# keyboard_68.net
KiCad netlist of a schematic drawn in Altium Designer
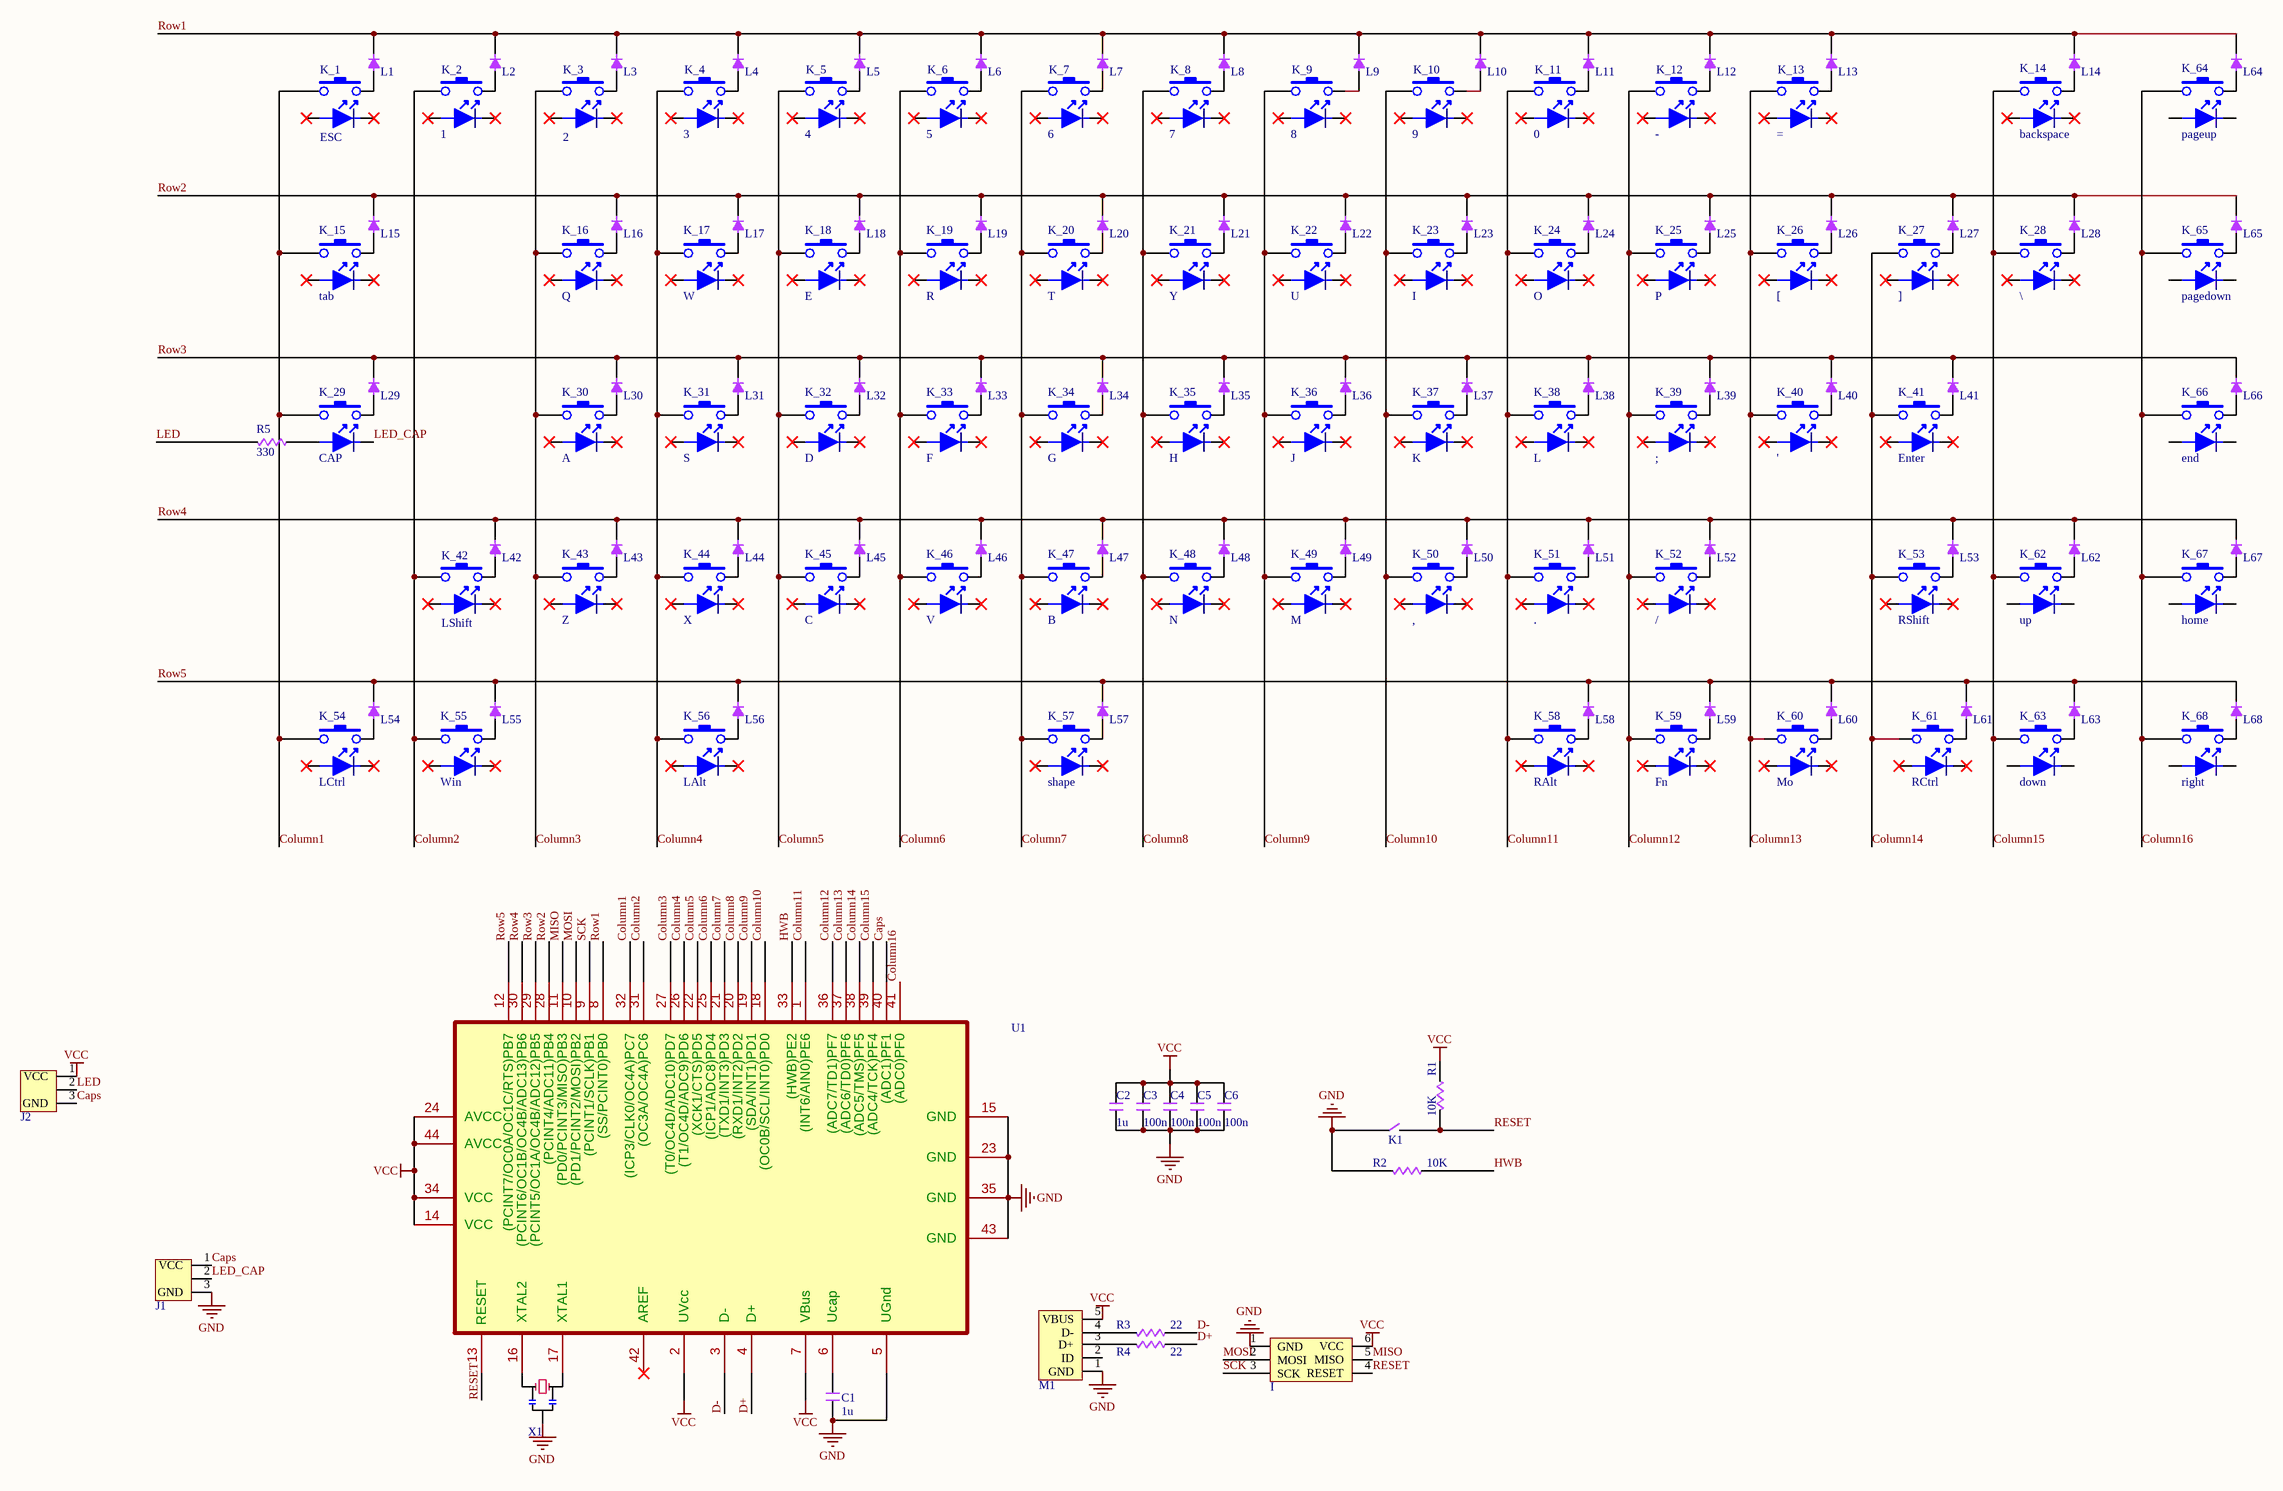
[diagram p0: keyboard_68.SchDoc]

(export (version "E")
  (design (tool "Eeschema 10.0.6"))
  (components
    (comp (ref "C1")
      (value "1u")
      (footprint "C_0603")
      (fields (field (name "Comment") "C"))
      (libsource (lib "Integrated_Library") (part "0603_C"))
    )
    (comp (ref "C2")
      (value "1u")
      (footprint "C_0603")
      (fields (field (name "Comment") "C"))
      (libsource (lib "Integrated_Library") (part "0603_C"))
    )
    (comp (ref "C3")
      (value "100n")
      (footprint "C_0603")
      (fields (field (name "Comment") "C"))
      (libsource (lib "Integrated_Library") (part "0603_C"))
    )
    (comp (ref "C4")
      (value "100n")
      (footprint "C_0603")
      (fields (field (name "Comment") "C"))
      (libsource (lib "Integrated_Library") (part "0603_C"))
    )
    (comp (ref "C5")
      (value "100n")
      (footprint "C_0603")
      (fields (field (name "Comment") "C"))
      (libsource (lib "Integrated_Library") (part "0603_C"))
    )
    (comp (ref "C6")
      (value "100n")
      (footprint "C_0603")
      (fields (field (name "Comment") "C"))
      (libsource (lib "Integrated_Library") (part "0603_C"))
    )
    (comp (ref "I") (value "ISP") (footprint "ISP") (libsource (lib "Integrated_Library") (part "ISP")))
    (comp (ref "J1") (value "Jump") (footprint "3PIN") (libsource (lib "Integrated_Library") (part "3PIN")))
    (comp (ref "J2") (value "Jump") (footprint "3PIN") (libsource (lib "Integrated_Library") (part "3PIN")))
    (comp (ref "K1") (value "SWITCH") (footprint "KEY") (libsource (lib "Integrated_Library") (part "KEY")))
    (comp (ref "K_1")
      (value "ESC")
      (footprint "CHERRY")
      (libsource (lib "Integrated_Library") (part "Cherry"))
    )
    (comp (ref "K_2") (value "1") (footprint "CHERRY") (libsource (lib "Integrated_Library") (part "Cherry")))
    (comp (ref "K_3") (value "2") (footprint "CHERRY") (libsource (lib "Integrated_Library") (part "Cherry")))
    (comp (ref "K_4") (value "3") (footprint "CHERRY") (libsource (lib "Integrated_Library") (part "Cherry")))
    (comp (ref "K_5") (value "4") (footprint "CHERRY") (libsource (lib "Integrated_Library") (part "Cherry")))
    (comp (ref "K_6") (value "5") (footprint "CHERRY") (libsource (lib "Integrated_Library") (part "Cherry")))
    (comp (ref "K_7") (value "6") (footprint "CHERRY") (libsource (lib "Integrated_Library") (part "Cherry")))
    (comp (ref "K_8") (value "7") (footprint "CHERRY") (libsource (lib "Integrated_Library") (part "Cherry")))
    (comp (ref "K_9") (value "8") (footprint "CHERRY") (libsource (lib "Integrated_Library") (part "Cherry")))
    (comp (ref "K_10")
      (value "9")
      (footprint "CHERRY")
      (libsource (lib "Integrated_Library") (part "Cherry"))
    )
    (comp (ref "K_11")
      (value "0")
      (footprint "CHERRY")
      (libsource (lib "Integrated_Library") (part "Cherry"))
    )
    (comp (ref "K_12")
      (value "-")
      (footprint "CHERRY")
      (libsource (lib "Integrated_Library") (part "Cherry"))
    )
    (comp (ref "K_13")
      (value "~")
      (footprint "CHERRY")
      (libsource (lib "Integrated_Library") (part "Cherry"))
    )
    (comp (ref "K_14")
      (value "backspace")
      (footprint "KEY_CAP")
      (libsource (lib "Integrated_Library") (part "SHIFT"))
    )
    (comp (ref "K_15")
      (value "tab")
      (footprint "CHERRY")
      (libsource (lib "Integrated_Library") (part "Cherry"))
    )
    (comp (ref "K_16")
      (value "Q")
      (footprint "CHERRY")
      (libsource (lib "Integrated_Library") (part "Cherry"))
    )
    (comp (ref "K_17")
      (value "W")
      (footprint "CHERRY")
      (libsource (lib "Integrated_Library") (part "Cherry"))
    )
    (comp (ref "K_18")
      (value "E")
      (footprint "CHERRY")
      (libsource (lib "Integrated_Library") (part "Cherry"))
    )
    (comp (ref "K_19")
      (value "R")
      (footprint "CHERRY")
      (libsource (lib "Integrated_Library") (part "Cherry"))
    )
    (comp (ref "K_20")
      (value "T")
      (footprint "CHERRY")
      (libsource (lib "Integrated_Library") (part "Cherry"))
    )
    (comp (ref "K_21")
      (value "Y")
      (footprint "CHERRY")
      (libsource (lib "Integrated_Library") (part "Cherry"))
    )
    (comp (ref "K_22")
      (value "U")
      (footprint "CHERRY")
      (libsource (lib "Integrated_Library") (part "Cherry"))
    )
    (comp (ref "K_23")
      (value "I")
      (footprint "CHERRY")
      (libsource (lib "Integrated_Library") (part "Cherry"))
    )
    (comp (ref "K_24")
      (value "O")
      (footprint "CHERRY")
      (libsource (lib "Integrated_Library") (part "Cherry"))
    )
    (comp (ref "K_25")
      (value "P")
      (footprint "CHERRY")
      (libsource (lib "Integrated_Library") (part "Cherry"))
    )
    (comp (ref "K_26")
      (value "[")
      (footprint "CHERRY")
      (libsource (lib "Integrated_Library") (part "Cherry"))
    )
    (comp (ref "K_27")
      (value "]")
      (footprint "CHERRY")
      (libsource (lib "Integrated_Library") (part "Cherry"))
    )
    (comp (ref "K_28")
      (value "\\")
      (footprint "CHERRY")
      (libsource (lib "Integrated_Library") (part "Cherry"))
    )
    (comp (ref "K_29")
      (value "CAP")
      (footprint "CHERRY")
      (libsource (lib "Integrated_Library") (part "Cherry"))
    )
    (comp (ref "K_30")
      (value "A")
      (footprint "CHERRY")
      (libsource (lib "Integrated_Library") (part "Cherry"))
    )
    (comp (ref "K_31")
      (value "S")
      (footprint "CHERRY")
      (libsource (lib "Integrated_Library") (part "Cherry"))
    )
    (comp (ref "K_32")
      (value "D")
      (footprint "CHERRY")
      (libsource (lib "Integrated_Library") (part "Cherry"))
    )
    (comp (ref "K_33")
      (value "F")
      (footprint "CHERRY")
      (libsource (lib "Integrated_Library") (part "Cherry"))
    )
    (comp (ref "K_34")
      (value "G")
      (footprint "CHERRY")
      (libsource (lib "Integrated_Library") (part "Cherry"))
    )
    (comp (ref "K_35")
      (value "H")
      (footprint "CHERRY")
      (libsource (lib "Integrated_Library") (part "Cherry"))
    )
    (comp (ref "K_36")
      (value "J")
      (footprint "CHERRY")
      (libsource (lib "Integrated_Library") (part "Cherry"))
    )
    (comp (ref "K_37")
      (value "K")
      (footprint "CHERRY")
      (libsource (lib "Integrated_Library") (part "Cherry"))
    )
    (comp (ref "K_38")
      (value "L")
      (footprint "CHERRY")
      (libsource (lib "Integrated_Library") (part "Cherry"))
    )
    (comp (ref "K_39")
      (value ";")
      (footprint "CHERRY")
      (libsource (lib "Integrated_Library") (part "Cherry"))
    )
    (comp (ref "K_40")
      (value "'")
      (footprint "CHERRY")
      (libsource (lib "Integrated_Library") (part "Cherry"))
    )
    (comp (ref "K_41")
      (value "Enter")
      (footprint "KEY_CAP")
      (libsource (lib "Integrated_Library") (part "SHIFT"))
    )
    (comp (ref "K_42")
      (value "LShift")
      (footprint "KEY_CAP")
      (libsource (lib "Integrated_Library") (part "SHIFT"))
    )
    (comp (ref "K_43")
      (value "Z")
      (footprint "CHERRY")
      (libsource (lib "Integrated_Library") (part "Cherry"))
    )
    (comp (ref "K_44")
      (value "X")
      (footprint "CHERRY")
      (libsource (lib "Integrated_Library") (part "Cherry"))
    )
    (comp (ref "K_45")
      (value "C")
      (footprint "CHERRY")
      (libsource (lib "Integrated_Library") (part "Cherry"))
    )
    (comp (ref "K_46")
      (value "V")
      (footprint "CHERRY")
      (libsource (lib "Integrated_Library") (part "Cherry"))
    )
    (comp (ref "K_47")
      (value "B")
      (footprint "CHERRY")
      (libsource (lib "Integrated_Library") (part "Cherry"))
    )
    (comp (ref "K_48")
      (value "N")
      (footprint "CHERRY")
      (libsource (lib "Integrated_Library") (part "Cherry"))
    )
    (comp (ref "K_49")
      (value "M")
      (footprint "CHERRY")
      (libsource (lib "Integrated_Library") (part "Cherry"))
    )
    (comp (ref "K_50")
      (value ",")
      (footprint "CHERRY")
      (libsource (lib "Integrated_Library") (part "Cherry"))
    )
    (comp (ref "K_51")
      (value ".")
      (footprint "CHERRY")
      (libsource (lib "Integrated_Library") (part "Cherry"))
    )
    (comp (ref "K_52")
      (value "/")
      (footprint "CHERRY")
      (libsource (lib "Integrated_Library") (part "Cherry"))
    )
    (comp (ref "K_53")
      (value "RShift")
      (footprint "KEY_CAP")
      (libsource (lib "Integrated_Library") (part "SHIFT"))
    )
    (comp (ref "K_54")
      (value "LCtrl")
      (footprint "CHERRY")
      (libsource (lib "Integrated_Library") (part "Cherry"))
    )
    (comp (ref "K_55")
      (value "Win")
      (footprint "CHERRY")
      (libsource (lib "Integrated_Library") (part "Cherry"))
    )
    (comp (ref "K_56")
      (value "LAlt")
      (footprint "CHERRY")
      (libsource (lib "Integrated_Library") (part "Cherry"))
    )
    (comp (ref "K_57")
      (value "shape")
      (footprint "SPACE_CAP")
      (libsource (lib "Integrated_Library") (part "shape"))
    )
    (comp (ref "K_58")
      (value "RAlt")
      (footprint "CHERRY")
      (libsource (lib "Integrated_Library") (part "Cherry"))
    )
    (comp (ref "K_59")
      (value "Fn")
      (footprint "CHERRY")
      (libsource (lib "Integrated_Library") (part "Cherry"))
    )
    (comp (ref "K_60")
      (value "Mo")
      (footprint "CHERRY")
      (libsource (lib "Integrated_Library") (part "Cherry"))
    )
    (comp (ref "K_61")
      (value "RCtrl")
      (footprint "CHERRY")
      (libsource (lib "Integrated_Library") (part "Cherry"))
    )
    (comp (ref "K_62")
      (value "up")
      (footprint "CHERRY")
      (libsource (lib "Integrated_Library") (part "Cherry"))
    )
    (comp (ref "K_63")
      (value "down")
      (footprint "CHERRY")
      (libsource (lib "Integrated_Library") (part "Cherry"))
    )
    (comp (ref "K_64")
      (value "pageup")
      (footprint "CHERRY")
      (libsource (lib "Integrated_Library") (part "Cherry"))
    )
    (comp (ref "K_65")
      (value "pagedown")
      (footprint "CHERRY")
      (libsource (lib "Integrated_Library") (part "Cherry"))
    )
    (comp (ref "K_66")
      (value "end")
      (footprint "CHERRY")
      (libsource (lib "Integrated_Library") (part "Cherry"))
    )
    (comp (ref "K_67")
      (value "home")
      (footprint "CHERRY")
      (libsource (lib "Integrated_Library") (part "Cherry"))
    )
    (comp (ref "K_68")
      (value "right")
      (footprint "CHERRY")
      (libsource (lib "Integrated_Library") (part "Cherry"))
    )
    (comp (ref "L1") (value "L") (footprint "L_0603") (libsource (lib "Integrated_Library") (part "0603_L")))
    (comp (ref "L2") (value "L") (footprint "L_0603") (libsource (lib "Integrated_Library") (part "0603_L")))
    (comp (ref "L3") (value "L") (footprint "L_0603") (libsource (lib "Integrated_Library") (part "0603_L")))
    (comp (ref "L4") (value "L") (footprint "L_0603") (libsource (lib "Integrated_Library") (part "0603_L")))
    (comp (ref "L5") (value "L") (footprint "L_0603") (libsource (lib "Integrated_Library") (part "0603_L")))
    (comp (ref "L6") (value "L") (footprint "L_0603") (libsource (lib "Integrated_Library") (part "0603_L")))
    (comp (ref "L7") (value "L") (footprint "L_0603") (libsource (lib "Integrated_Library") (part "0603_L")))
    (comp (ref "L8") (value "L") (footprint "L_0603") (libsource (lib "Integrated_Library") (part "0603_L")))
    (comp (ref "L9") (value "L") (footprint "L_0603") (libsource (lib "Integrated_Library") (part "0603_L")))
    (comp (ref "L10") (value "L") (footprint "L_0603") (libsource (lib "Integrated_Library") (part "0603_L")))
    (comp (ref "L11") (value "L") (footprint "L_0603") (libsource (lib "Integrated_Library") (part "0603_L")))
    (comp (ref "L12") (value "L") (footprint "L_0603") (libsource (lib "Integrated_Library") (part "0603_L")))
    (comp (ref "L13") (value "L") (footprint "L_0603") (libsource (lib "Integrated_Library") (part "0603_L")))
    (comp (ref "L14") (value "L") (footprint "L_0603") (libsource (lib "Integrated_Library") (part "0603_L")))
    (comp (ref "L15") (value "L") (footprint "L_0603") (libsource (lib "Integrated_Library") (part "0603_L")))
    (comp (ref "L16") (value "L") (footprint "L_0603") (libsource (lib "Integrated_Library") (part "0603_L")))
    (comp (ref "L17") (value "L") (footprint "L_0603") (libsource (lib "Integrated_Library") (part "0603_L")))
    (comp (ref "L18") (value "L") (footprint "L_0603") (libsource (lib "Integrated_Library") (part "0603_L")))
    (comp (ref "L19") (value "L") (footprint "L_0603") (libsource (lib "Integrated_Library") (part "0603_L")))
    (comp (ref "L20") (value "L") (footprint "L_0603") (libsource (lib "Integrated_Library") (part "0603_L")))
    (comp (ref "L21") (value "L") (footprint "L_0603") (libsource (lib "Integrated_Library") (part "0603_L")))
    (comp (ref "L22") (value "L") (footprint "L_0603") (libsource (lib "Integrated_Library") (part "0603_L")))
    (comp (ref "L23") (value "L") (footprint "L_0603") (libsource (lib "Integrated_Library") (part "0603_L")))
    (comp (ref "L24") (value "L") (footprint "L_0603") (libsource (lib "Integrated_Library") (part "0603_L")))
    (comp (ref "L25") (value "L") (footprint "L_0603") (libsource (lib "Integrated_Library") (part "0603_L")))
    (comp (ref "L26") (value "L") (footprint "L_0603") (libsource (lib "Integrated_Library") (part "0603_L")))
    (comp (ref "L27") (value "L") (footprint "L_0603") (libsource (lib "Integrated_Library") (part "0603_L")))
    (comp (ref "L28") (value "L") (footprint "L_0603") (libsource (lib "Integrated_Library") (part "0603_L")))
    (comp (ref "L29") (value "L") (footprint "L_0603") (libsource (lib "Integrated_Library") (part "0603_L")))
    (comp (ref "L30") (value "L") (footprint "L_0603") (libsource (lib "Integrated_Library") (part "0603_L")))
    (comp (ref "L31") (value "L") (footprint "L_0603") (libsource (lib "Integrated_Library") (part "0603_L")))
    (comp (ref "L32") (value "L") (footprint "L_0603") (libsource (lib "Integrated_Library") (part "0603_L")))
    (comp (ref "L33") (value "L") (footprint "L_0603") (libsource (lib "Integrated_Library") (part "0603_L")))
    (comp (ref "L34") (value "L") (footprint "L_0603") (libsource (lib "Integrated_Library") (part "0603_L")))
    (comp (ref "L35") (value "L") (footprint "L_0603") (libsource (lib "Integrated_Library") (part "0603_L")))
    (comp (ref "L36") (value "L") (footprint "L_0603") (libsource (lib "Integrated_Library") (part "0603_L")))
    (comp (ref "L37") (value "L") (footprint "L_0603") (libsource (lib "Integrated_Library") (part "0603_L")))
    (comp (ref "L38") (value "L") (footprint "L_0603") (libsource (lib "Integrated_Library") (part "0603_L")))
    (comp (ref "L39") (value "L") (footprint "L_0603") (libsource (lib "Integrated_Library") (part "0603_L")))
    (comp (ref "L40") (value "L") (footprint "L_0603") (libsource (lib "Integrated_Library") (part "0603_L")))
    (comp (ref "L41") (value "L") (footprint "L_0603") (libsource (lib "Integrated_Library") (part "0603_L")))
    (comp (ref "L42") (value "L") (footprint "L_0603") (libsource (lib "Integrated_Library") (part "0603_L")))
    (comp (ref "L43") (value "L") (footprint "L_0603") (libsource (lib "Integrated_Library") (part "0603_L")))
    (comp (ref "L44") (value "L") (footprint "L_0603") (libsource (lib "Integrated_Library") (part "0603_L")))
    (comp (ref "L45") (value "L") (footprint "L_0603") (libsource (lib "Integrated_Library") (part "0603_L")))
    (comp (ref "L46") (value "L") (footprint "L_0603") (libsource (lib "Integrated_Library") (part "0603_L")))
    (comp (ref "L47") (value "L") (footprint "L_0603") (libsource (lib "Integrated_Library") (part "0603_L")))
    (comp (ref "L48") (value "L") (footprint "L_0603") (libsource (lib "Integrated_Library") (part "0603_L")))
    (comp (ref "L49") (value "L") (footprint "L_0603") (libsource (lib "Integrated_Library") (part "0603_L")))
    (comp (ref "L50") (value "L") (footprint "L_0603") (libsource (lib "Integrated_Library") (part "0603_L")))
    (comp (ref "L51") (value "L") (footprint "L_0603") (libsource (lib "Integrated_Library") (part "0603_L")))
    (comp (ref "L52") (value "L") (footprint "L_0603") (libsource (lib "Integrated_Library") (part "0603_L")))
    (comp (ref "L53") (value "L") (footprint "L_0603") (libsource (lib "Integrated_Library") (part "0603_L")))
    (comp (ref "L54") (value "L") (footprint "L_0603") (libsource (lib "Integrated_Library") (part "0603_L")))
    (comp (ref "L55") (value "L") (footprint "L_0603") (libsource (lib "Integrated_Library") (part "0603_L")))
    (comp (ref "L56") (value "L") (footprint "L_0603") (libsource (lib "Integrated_Library") (part "0603_L")))
    (comp (ref "L57") (value "L") (footprint "L_0603") (libsource (lib "Integrated_Library") (part "0603_L")))
    (comp (ref "L58") (value "L") (footprint "L_0603") (libsource (lib "Integrated_Library") (part "0603_L")))
    (comp (ref "L59") (value "L") (footprint "L_0603") (libsource (lib "Integrated_Library") (part "0603_L")))
    (comp (ref "L60") (value "L") (footprint "L_0603") (libsource (lib "Integrated_Library") (part "0603_L")))
    (comp (ref "L61") (value "L") (footprint "L_0603") (libsource (lib "Integrated_Library") (part "0603_L")))
    (comp (ref "L62") (value "L") (footprint "L_0603") (libsource (lib "Integrated_Library") (part "0603_L")))
    (comp (ref "L63") (value "L") (footprint "L_0603") (libsource (lib "Integrated_Library") (part "0603_L")))
    (comp (ref "L64") (value "L") (footprint "L_0603") (libsource (lib "Integrated_Library") (part "0603_L")))
    (comp (ref "L65") (value "L") (footprint "L_0603") (libsource (lib "Integrated_Library") (part "0603_L")))
    (comp (ref "L66") (value "L") (footprint "L_0603") (libsource (lib "Integrated_Library") (part "0603_L")))
    (comp (ref "L67") (value "L") (footprint "L_0603") (libsource (lib "Integrated_Library") (part "0603_L")))
    (comp (ref "L68") (value "L") (footprint "L_0603") (libsource (lib "Integrated_Library") (part "0603_L")))
    (comp (ref "M1")
      (value "USB")
      (footprint "MICRO_USB")
      (libsource (lib "Integrated_Library") (part "MICRO_USB"))
    )
    (comp (ref "R1")
      (value "10K")
      (footprint "R_0603")
      (fields (field (name "Comment") "R"))
      (libsource (lib "Integrated_Library") (part "0603_R"))
    )
    (comp (ref "R2")
      (value "10K")
      (footprint "R_0603")
      (fields (field (name "Comment") "R"))
      (libsource (lib "Integrated_Library") (part "0603_R"))
    )
    (comp (ref "R3")
      (value "22")
      (footprint "R_0603")
      (fields (field (name "Comment") "R"))
      (libsource (lib "Integrated_Library") (part "0603_R"))
    )
    (comp (ref "R4")
      (value "22")
      (footprint "R_0603")
      (fields (field (name "Comment") "R"))
      (libsource (lib "Integrated_Library") (part "0603_R"))
    )
    (comp (ref "R5")
      (value "330")
      (footprint "R_0603")
      (fields (field (name "Comment") "R"))
      (libsource (lib "") (part "0603_R_1"))
    )
    (comp (ref "U1")
      (value "Atmega32U4")
      (footprint "TQFP80P1200X1200X120-44N")
      (libsource (lib "Integrated_Library") (part "LQFP44(ATMEGA32U4)"))
    )
    (comp (ref "X1")
      (value "CSTCE")
      (footprint "CSTCE")
      (libsource (lib "Integrated_Library") (part "CSTCE"))
    )
  )
  (nets
    (net (code "1") (name "/Caps") (class "Default")
      (node (ref "J1") (pin "1") (pinfunction "VCC_1") (pintype "passive"))
      (node (ref "J2") (pin "3") (pinfunction "GND_3") (pintype "passive"))
      (node (ref "U1") (pin "40") (pinfunction "(ADC1)PF1_40") (pintype "passive"))
    )
    (net (code "2") (name "/Column1") (class "Default")
      (node (ref "K_1") (pin "1") (pinfunction "1_1") (pintype "passive"))
      (node (ref "K_15") (pin "1") (pinfunction "1_1") (pintype "passive"))
      (node (ref "K_29") (pin "1") (pinfunction "1_1") (pintype "passive"))
      (node (ref "K_54") (pin "1") (pinfunction "1_1") (pintype "passive"))
      (node (ref "U1") (pin "32") (pinfunction "(ICP3/CLK0/OC4A)PC7_32") (pintype "passive"))
    )
    (net (code "3") (name "/Column2") (class "Default")
      (node (ref "K_2") (pin "1") (pinfunction "1_1") (pintype "passive"))
      (node (ref "K_42") (pin "1") (pinfunction "1_1") (pintype "passive"))
      (node (ref "K_55") (pin "1") (pinfunction "1_1") (pintype "passive"))
      (node (ref "U1") (pin "31") (pinfunction "(OC3A/OC4A)PC6_31") (pintype "passive"))
    )
    (net (code "4") (name "/Column3") (class "Default")
      (node (ref "K_16") (pin "1") (pinfunction "1_1") (pintype "passive"))
      (node (ref "K_3") (pin "1") (pinfunction "1_1") (pintype "passive"))
      (node (ref "K_30") (pin "1") (pinfunction "1_1") (pintype "passive"))
      (node (ref "K_43") (pin "1") (pinfunction "1_1") (pintype "passive"))
      (node (ref "U1") (pin "27") (pinfunction "(T0/OC4D/ADC10)PD7_27") (pintype "passive"))
    )
    (net (code "5") (name "/Column4") (class "Default")
      (node (ref "K_17") (pin "1") (pinfunction "1_1") (pintype "passive"))
      (node (ref "K_31") (pin "1") (pinfunction "1_1") (pintype "passive"))
      (node (ref "K_4") (pin "1") (pinfunction "1_1") (pintype "passive"))
      (node (ref "K_44") (pin "1") (pinfunction "1_1") (pintype "passive"))
      (node (ref "K_56") (pin "1") (pinfunction "1_1") (pintype "passive"))
      (node (ref "U1") (pin "26") (pinfunction "(T1/OC4D/ADC9)PD6_26") (pintype "passive"))
    )
    (net (code "6") (name "/Column5") (class "Default")
      (node (ref "K_18") (pin "1") (pinfunction "1_1") (pintype "passive"))
      (node (ref "K_32") (pin "1") (pinfunction "1_1") (pintype "passive"))
      (node (ref "K_45") (pin "1") (pinfunction "1_1") (pintype "passive"))
      (node (ref "K_5") (pin "1") (pinfunction "1_1") (pintype "passive"))
      (node (ref "U1") (pin "22") (pinfunction "(XCK1/CTS)PD5_22") (pintype "passive"))
    )
    (net (code "7") (name "/Column6") (class "Default")
      (node (ref "K_19") (pin "1") (pinfunction "1_1") (pintype "passive"))
      (node (ref "K_33") (pin "1") (pinfunction "1_1") (pintype "passive"))
      (node (ref "K_46") (pin "1") (pinfunction "1_1") (pintype "passive"))
      (node (ref "K_6") (pin "1") (pinfunction "1_1") (pintype "passive"))
      (node (ref "U1") (pin "25") (pinfunction "(ICP1/ADC8)PD4_25") (pintype "passive"))
    )
    (net (code "8") (name "/Column7") (class "Default")
      (node (ref "K_20") (pin "1") (pinfunction "1_1") (pintype "passive"))
      (node (ref "K_34") (pin "1") (pinfunction "1_1") (pintype "passive"))
      (node (ref "K_47") (pin "1") (pinfunction "1_1") (pintype "passive"))
      (node (ref "K_57") (pin "1") (pinfunction "1_1") (pintype "passive"))
      (node (ref "K_7") (pin "1") (pinfunction "1_1") (pintype "passive"))
      (node (ref "U1") (pin "21") (pinfunction "(TXD1/INT3)PD3_21") (pintype "passive"))
    )
    (net (code "9") (name "/Column8") (class "Default")
      (node (ref "K_21") (pin "1") (pinfunction "1_1") (pintype "passive"))
      (node (ref "K_35") (pin "1") (pinfunction "1_1") (pintype "passive"))
      (node (ref "K_48") (pin "1") (pinfunction "1_1") (pintype "passive"))
      (node (ref "K_8") (pin "1") (pinfunction "1_1") (pintype "passive"))
      (node (ref "U1") (pin "20") (pinfunction "(RXD1/INT2)PD2_20") (pintype "passive"))
    )
    (net (code "10") (name "/Column9") (class "Default")
      (node (ref "K_22") (pin "1") (pinfunction "1_1") (pintype "passive"))
      (node (ref "K_36") (pin "1") (pinfunction "1_1") (pintype "passive"))
      (node (ref "K_49") (pin "1") (pinfunction "1_1") (pintype "passive"))
      (node (ref "K_9") (pin "1") (pinfunction "1_1") (pintype "passive"))
      (node (ref "U1") (pin "19") (pinfunction "(SDA/INT1)PD1_19") (pintype "passive"))
    )
    (net (code "11") (name "/Column10") (class "Default")
      (node (ref "K_10") (pin "1") (pinfunction "1_1") (pintype "passive"))
      (node (ref "K_23") (pin "1") (pinfunction "1_1") (pintype "passive"))
      (node (ref "K_37") (pin "1") (pinfunction "1_1") (pintype "passive"))
      (node (ref "K_50") (pin "1") (pinfunction "1_1") (pintype "passive"))
      (node (ref "U1") (pin "18") (pinfunction "(OC0B/SCL/INT0)PD0_18") (pintype "passive"))
    )
    (net (code "12") (name "/Column11") (class "Default")
      (node (ref "K_11") (pin "1") (pinfunction "1_1") (pintype "passive"))
      (node (ref "K_24") (pin "1") (pinfunction "1_1") (pintype "passive"))
      (node (ref "K_38") (pin "1") (pinfunction "1_1") (pintype "passive"))
      (node (ref "K_51") (pin "1") (pinfunction "1_1") (pintype "passive"))
      (node (ref "K_58") (pin "1") (pinfunction "1_1") (pintype "passive"))
      (node (ref "U1") (pin "1") (pinfunction "(INT6/AIN0)PE6_1") (pintype "passive"))
    )
    (net (code "13") (name "/Column12") (class "Default")
      (node (ref "K_12") (pin "1") (pinfunction "1_1") (pintype "passive"))
      (node (ref "K_25") (pin "1") (pinfunction "1_1") (pintype "passive"))
      (node (ref "K_39") (pin "1") (pinfunction "1_1") (pintype "passive"))
      (node (ref "K_52") (pin "1") (pinfunction "1_1") (pintype "passive"))
      (node (ref "K_59") (pin "1") (pinfunction "1_1") (pintype "passive"))
      (node (ref "U1") (pin "36") (pinfunction "(ADC7/TD1)PF7_36") (pintype "passive"))
    )
    (net (code "14") (name "/Column13") (class "Default")
      (node (ref "K_13") (pin "1") (pinfunction "1_1") (pintype "passive"))
      (node (ref "K_26") (pin "1") (pinfunction "1_1") (pintype "passive"))
      (node (ref "K_40") (pin "1") (pinfunction "1_1") (pintype "passive"))
      (node (ref "K_60") (pin "1") (pinfunction "1_1") (pintype "passive"))
      (node (ref "U1") (pin "37") (pinfunction "(ADC6/TD0)PF6_37") (pintype "passive"))
    )
    (net (code "15") (name "/Column14") (class "Default")
      (node (ref "K_27") (pin "1") (pinfunction "1_1") (pintype "passive"))
      (node (ref "K_41") (pin "1") (pinfunction "1_1") (pintype "passive"))
      (node (ref "K_53") (pin "1") (pinfunction "1_1") (pintype "passive"))
      (node (ref "K_61") (pin "1") (pinfunction "1_1") (pintype "passive"))
      (node (ref "U1") (pin "38") (pinfunction "(ADC5/TMS)PF5_38") (pintype "passive"))
    )
    (net (code "16") (name "/Column15") (class "Default")
      (node (ref "K_14") (pin "1") (pinfunction "1_1") (pintype "passive"))
      (node (ref "K_28") (pin "1") (pinfunction "1_1") (pintype "passive"))
      (node (ref "K_62") (pin "1") (pinfunction "1_1") (pintype "passive"))
      (node (ref "K_63") (pin "1") (pinfunction "1_1") (pintype "passive"))
      (node (ref "U1") (pin "39") (pinfunction "(ADC4/TCK)PF4_39") (pintype "passive"))
    )
    (net (code "17") (name "/Column16") (class "Default")
      (node (ref "K_64") (pin "1") (pinfunction "1_1") (pintype "passive"))
      (node (ref "K_65") (pin "1") (pinfunction "1_1") (pintype "passive"))
      (node (ref "K_66") (pin "1") (pinfunction "1_1") (pintype "passive"))
      (node (ref "K_67") (pin "1") (pinfunction "1_1") (pintype "passive"))
      (node (ref "K_68") (pin "1") (pinfunction "1_1") (pintype "passive"))
      (node (ref "U1") (pin "41") (pinfunction "(ADC0)PF0_41") (pintype "passive"))
    )
    (net (code "18") (name "/D+") (class "Default")
      (node (ref "R4") (pin "2") (pintype "passive"))
      (node (ref "U1") (pin "4") (pinfunction "D+_4") (pintype "passive"))
    )
    (net (code "19") (name "/D-") (class "Default")
      (node (ref "R3") (pin "2") (pintype "passive"))
      (node (ref "U1") (pin "3") (pinfunction "D-_3") (pintype "passive"))
    )
    (net (code "20") (name "/HWB") (class "Default")
      (node (ref "R2") (pin "2") (pintype "passive"))
      (node (ref "U1") (pin "33") (pinfunction "(HWB)PE2_33") (pintype "passive"))
    )
    (net (code "21") (name "/LED") (class "Default")
      (node (ref "J2") (pin "2") (pinfunction "MISO_2") (pintype "passive"))
      (node (ref "R5") (pin "1") (pintype "passive"))
    )
    (net (code "22") (name "/LED_CAP") (class "Default")
      (node (ref "J1") (pin "2") (pinfunction "MISO_2") (pintype "passive"))
      (node (ref "K_29") (pin "4") (pinfunction "4_4") (pintype "passive"))
    )
    (net (code "23") (name "/MISO") (class "Default")
      (node (ref "I") (pin "5") (pinfunction "MISO_5") (pintype "passive"))
      (node (ref "U1") (pin "11") (pinfunction "(PD0/PCINT3/MISO)PB3_11") (pintype "passive"))
    )
    (net (code "24") (name "/MOSI") (class "Default")
      (node (ref "I") (pin "2") (pinfunction "MOSI_2") (pintype "passive"))
      (node (ref "U1") (pin "10") (pinfunction "(PD1/PCINT2/MOSI)PB2_10") (pintype "passive"))
    )
    (net (code "25") (name "/RESET") (class "Default")
      (node (ref "I") (pin "4") (pinfunction "RESET_4") (pintype "passive"))
      (node (ref "K1") (pin "2") (pinfunction "off_2") (pintype "passive"))
      (node (ref "R1") (pin "1") (pintype "passive"))
      (node (ref "U1") (pin "13") (pinfunction "RESET_13") (pintype "passive"))
    )
    (net (code "26") (name "/Row1") (class "Default")
      (node (ref "L1") (pin "2") (pintype "passive"))
      (node (ref "L10") (pin "2") (pintype "passive"))
      (node (ref "L11") (pin "2") (pintype "passive"))
      (node (ref "L12") (pin "2") (pintype "passive"))
      (node (ref "L13") (pin "2") (pintype "passive"))
      (node (ref "L14") (pin "2") (pintype "passive"))
      (node (ref "L2") (pin "2") (pintype "passive"))
      (node (ref "L3") (pin "2") (pintype "passive"))
      (node (ref "L4") (pin "2") (pintype "passive"))
      (node (ref "L5") (pin "2") (pintype "passive"))
      (node (ref "L6") (pin "2") (pintype "passive"))
      (node (ref "L64") (pin "2") (pintype "passive"))
      (node (ref "L7") (pin "2") (pintype "passive"))
      (node (ref "L8") (pin "2") (pintype "passive"))
      (node (ref "L9") (pin "2") (pintype "passive"))
      (node (ref "U1") (pin "8") (pinfunction "(SS/PCINT0)PB0_8") (pintype "passive"))
    )
    (net (code "27") (name "/Row2") (class "Default")
      (node (ref "L15") (pin "2") (pintype "passive"))
      (node (ref "L16") (pin "2") (pintype "passive"))
      (node (ref "L17") (pin "2") (pintype "passive"))
      (node (ref "L18") (pin "2") (pintype "passive"))
      (node (ref "L19") (pin "2") (pintype "passive"))
      (node (ref "L20") (pin "2") (pintype "passive"))
      (node (ref "L21") (pin "2") (pintype "passive"))
      (node (ref "L22") (pin "2") (pintype "passive"))
      (node (ref "L23") (pin "2") (pintype "passive"))
      (node (ref "L24") (pin "2") (pintype "passive"))
      (node (ref "L25") (pin "2") (pintype "passive"))
      (node (ref "L26") (pin "2") (pintype "passive"))
      (node (ref "L27") (pin "2") (pintype "passive"))
      (node (ref "L28") (pin "2") (pintype "passive"))
      (node (ref "L65") (pin "2") (pintype "passive"))
      (node (ref "U1") (pin "28") (pinfunction "(PCINT4/ADC11)PB4_28") (pintype "passive"))
    )
    (net (code "28") (name "/Row3") (class "Default")
      (node (ref "L29") (pin "2") (pintype "passive"))
      (node (ref "L30") (pin "2") (pintype "passive"))
      (node (ref "L31") (pin "2") (pintype "passive"))
      (node (ref "L32") (pin "2") (pintype "passive"))
      (node (ref "L33") (pin "2") (pintype "passive"))
      (node (ref "L34") (pin "2") (pintype "passive"))
      (node (ref "L35") (pin "2") (pintype "passive"))
      (node (ref "L36") (pin "2") (pintype "passive"))
      (node (ref "L37") (pin "2") (pintype "passive"))
      (node (ref "L38") (pin "2") (pintype "passive"))
      (node (ref "L39") (pin "2") (pintype "passive"))
      (node (ref "L40") (pin "2") (pintype "passive"))
      (node (ref "L41") (pin "2") (pintype "passive"))
      (node (ref "L66") (pin "2") (pintype "passive"))
      (node (ref "U1") (pin "29") (pinfunction "(PCINT5/OC1A/OC4B/ADC12)PB5_29") (pintype "passive"))
    )
    (net (code "29") (name "/Row4") (class "Default")
      (node (ref "L42") (pin "2") (pintype "passive"))
      (node (ref "L43") (pin "2") (pintype "passive"))
      (node (ref "L44") (pin "2") (pintype "passive"))
      (node (ref "L45") (pin "2") (pintype "passive"))
      (node (ref "L46") (pin "2") (pintype "passive"))
      (node (ref "L47") (pin "2") (pintype "passive"))
      (node (ref "L48") (pin "2") (pintype "passive"))
      (node (ref "L49") (pin "2") (pintype "passive"))
      (node (ref "L50") (pin "2") (pintype "passive"))
      (node (ref "L51") (pin "2") (pintype "passive"))
      (node (ref "L52") (pin "2") (pintype "passive"))
      (node (ref "L53") (pin "2") (pintype "passive"))
      (node (ref "L62") (pin "2") (pintype "passive"))
      (node (ref "L67") (pin "2") (pintype "passive"))
      (node (ref "U1") (pin "30") (pinfunction "(PCINT6/OC1B/OC4B/ADC13)PB6_30") (pintype "passive"))
    )
    (net (code "30") (name "/Row5") (class "Default")
      (node (ref "L54") (pin "2") (pintype "passive"))
      (node (ref "L55") (pin "2") (pintype "passive"))
      (node (ref "L56") (pin "2") (pintype "passive"))
      (node (ref "L57") (pin "2") (pintype "passive"))
      (node (ref "L58") (pin "2") (pintype "passive"))
      (node (ref "L59") (pin "2") (pintype "passive"))
      (node (ref "L60") (pin "2") (pintype "passive"))
      (node (ref "L61") (pin "2") (pintype "passive"))
      (node (ref "L63") (pin "2") (pintype "passive"))
      (node (ref "L68") (pin "2") (pintype "passive"))
      (node (ref "U1") (pin "12") (pinfunction "(PCINT7/OC0A/OC1C/RTS)PB7_12") (pintype "passive"))
    )
    (net (code "31") (name "/SCK") (class "Default")
      (node (ref "I") (pin "3") (pinfunction "SCK_3") (pintype "passive"))
      (node (ref "U1") (pin "9") (pinfunction "(PCINT1/SCLK)PB1_9") (pintype "passive"))
    )
    (net (code "32") (name "GND") (class "Default")
      (node (ref "C1") (pin "1") (pintype "passive"))
      (node (ref "C2") (pin "1") (pintype "passive"))
      (node (ref "C3") (pin "1") (pintype "passive"))
      (node (ref "C4") (pin "1") (pintype "passive"))
      (node (ref "C5") (pin "1") (pintype "passive"))
      (node (ref "C6") (pin "1") (pintype "passive"))
      (node (ref "I") (pin "1") (pinfunction "GND_1") (pintype "passive"))
      (node (ref "J1") (pin "3") (pinfunction "GND_3") (pintype "passive"))
      (node (ref "K1") (pin "1") (pinfunction "on_1") (pintype "passive"))
      (node (ref "M1") (pin "1") (pinfunction "GND_1") (pintype "passive"))
      (node (ref "R2") (pin "1") (pintype "passive"))
      (node (ref "U1") (pin "15") (pinfunction "GND_15") (pintype "passive"))
      (node (ref "U1") (pin "23") (pinfunction "GND_23") (pintype "passive"))
      (node (ref "U1") (pin "35") (pinfunction "GND_35") (pintype "passive"))
      (node (ref "U1") (pin "43") (pinfunction "GND_43") (pintype "passive"))
      (node (ref "U1") (pin "5") (pinfunction "UGnd_5") (pintype "passive"))
      (node (ref "X1") (pin "2") (pinfunction "GND_2") (pintype "passive"))
    )
    (net (code "33") (name "Net-(K_29-Pad3)") (class "Default")
      (node (ref "K_29") (pin "3") (pinfunction "3_3") (pintype "passive"))
      (node (ref "R5") (pin "2") (pintype "passive"))
    )
    (net (code "34") (name "Net-(L1-+)") (class "Default")
      (node (ref "K_1") (pin "2") (pinfunction "2_2") (pintype "passive"))
      (node (ref "L1") (pin "1") (pinfunction "+_1") (pintype "passive"))
    )
    (net (code "35") (name "Net-(L2-+)") (class "Default")
      (node (ref "K_2") (pin "2") (pinfunction "2_2") (pintype "passive"))
      (node (ref "L2") (pin "1") (pinfunction "+_1") (pintype "passive"))
    )
    (net (code "36") (name "Net-(L3-+)") (class "Default")
      (node (ref "K_3") (pin "2") (pinfunction "2_2") (pintype "passive"))
      (node (ref "L3") (pin "1") (pinfunction "+_1") (pintype "passive"))
    )
    (net (code "37") (name "Net-(L4-+)") (class "Default")
      (node (ref "K_4") (pin "2") (pinfunction "2_2") (pintype "passive"))
      (node (ref "L4") (pin "1") (pinfunction "+_1") (pintype "passive"))
    )
    (net (code "38") (name "Net-(L5-+)") (class "Default")
      (node (ref "K_5") (pin "2") (pinfunction "2_2") (pintype "passive"))
      (node (ref "L5") (pin "1") (pinfunction "+_1") (pintype "passive"))
    )
    (net (code "39") (name "Net-(L6-+)") (class "Default")
      (node (ref "K_6") (pin "2") (pinfunction "2_2") (pintype "passive"))
      (node (ref "L6") (pin "1") (pinfunction "+_1") (pintype "passive"))
    )
    (net (code "40") (name "Net-(L7-+)") (class "Default")
      (node (ref "K_7") (pin "2") (pinfunction "2_2") (pintype "passive"))
      (node (ref "L7") (pin "1") (pinfunction "+_1") (pintype "passive"))
    )
    (net (code "41") (name "Net-(L8-+)") (class "Default")
      (node (ref "K_8") (pin "2") (pinfunction "2_2") (pintype "passive"))
      (node (ref "L8") (pin "1") (pinfunction "+_1") (pintype "passive"))
    )
    (net (code "42") (name "Net-(L9-+)") (class "Default")
      (node (ref "K_9") (pin "2") (pinfunction "2_2") (pintype "passive"))
      (node (ref "L9") (pin "1") (pinfunction "+_1") (pintype "passive"))
    )
    (net (code "43") (name "Net-(L10-+)") (class "Default")
      (node (ref "K_10") (pin "2") (pinfunction "2_2") (pintype "passive"))
      (node (ref "L10") (pin "1") (pinfunction "+_1") (pintype "passive"))
    )
    (net (code "44") (name "Net-(L11-+)") (class "Default")
      (node (ref "K_11") (pin "2") (pinfunction "2_2") (pintype "passive"))
      (node (ref "L11") (pin "1") (pinfunction "+_1") (pintype "passive"))
    )
    (net (code "45") (name "Net-(L12-+)") (class "Default")
      (node (ref "K_12") (pin "2") (pinfunction "2_2") (pintype "passive"))
      (node (ref "L12") (pin "1") (pinfunction "+_1") (pintype "passive"))
    )
    (net (code "46") (name "Net-(L13-+)") (class "Default")
      (node (ref "K_13") (pin "2") (pinfunction "2_2") (pintype "passive"))
      (node (ref "L13") (pin "1") (pinfunction "+_1") (pintype "passive"))
    )
    (net (code "47") (name "Net-(L14-+)") (class "Default")
      (node (ref "K_14") (pin "2") (pinfunction "2_2") (pintype "passive"))
      (node (ref "L14") (pin "1") (pinfunction "+_1") (pintype "passive"))
    )
    (net (code "48") (name "Net-(L15-+)") (class "Default")
      (node (ref "K_15") (pin "2") (pinfunction "2_2") (pintype "passive"))
      (node (ref "L15") (pin "1") (pinfunction "+_1") (pintype "passive"))
    )
    (net (code "49") (name "Net-(L16-+)") (class "Default")
      (node (ref "K_16") (pin "2") (pinfunction "2_2") (pintype "passive"))
      (node (ref "L16") (pin "1") (pinfunction "+_1") (pintype "passive"))
    )
    (net (code "50") (name "Net-(L17-+)") (class "Default")
      (node (ref "K_17") (pin "2") (pinfunction "2_2") (pintype "passive"))
      (node (ref "L17") (pin "1") (pinfunction "+_1") (pintype "passive"))
    )
    (net (code "51") (name "Net-(L18-+)") (class "Default")
      (node (ref "K_18") (pin "2") (pinfunction "2_2") (pintype "passive"))
      (node (ref "L18") (pin "1") (pinfunction "+_1") (pintype "passive"))
    )
    (net (code "52") (name "Net-(L19-+)") (class "Default")
      (node (ref "K_19") (pin "2") (pinfunction "2_2") (pintype "passive"))
      (node (ref "L19") (pin "1") (pinfunction "+_1") (pintype "passive"))
    )
    (net (code "53") (name "Net-(L20-+)") (class "Default")
      (node (ref "K_20") (pin "2") (pinfunction "2_2") (pintype "passive"))
      (node (ref "L20") (pin "1") (pinfunction "+_1") (pintype "passive"))
    )
    (net (code "54") (name "Net-(L21-+)") (class "Default")
      (node (ref "K_21") (pin "2") (pinfunction "2_2") (pintype "passive"))
      (node (ref "L21") (pin "1") (pinfunction "+_1") (pintype "passive"))
    )
    (net (code "55") (name "Net-(L22-+)") (class "Default")
      (node (ref "K_22") (pin "2") (pinfunction "2_2") (pintype "passive"))
      (node (ref "L22") (pin "1") (pinfunction "+_1") (pintype "passive"))
    )
    (net (code "56") (name "Net-(L23-+)") (class "Default")
      (node (ref "K_23") (pin "2") (pinfunction "2_2") (pintype "passive"))
      (node (ref "L23") (pin "1") (pinfunction "+_1") (pintype "passive"))
    )
    (net (code "57") (name "Net-(L24-+)") (class "Default")
      (node (ref "K_24") (pin "2") (pinfunction "2_2") (pintype "passive"))
      (node (ref "L24") (pin "1") (pinfunction "+_1") (pintype "passive"))
    )
    (net (code "58") (name "Net-(L25-+)") (class "Default")
      (node (ref "K_25") (pin "2") (pinfunction "2_2") (pintype "passive"))
      (node (ref "L25") (pin "1") (pinfunction "+_1") (pintype "passive"))
    )
    (net (code "59") (name "Net-(L26-+)") (class "Default")
      (node (ref "K_26") (pin "2") (pinfunction "2_2") (pintype "passive"))
      (node (ref "L26") (pin "1") (pinfunction "+_1") (pintype "passive"))
    )
    (net (code "60") (name "Net-(L27-+)") (class "Default")
      (node (ref "K_27") (pin "2") (pinfunction "2_2") (pintype "passive"))
      (node (ref "L27") (pin "1") (pinfunction "+_1") (pintype "passive"))
    )
    (net (code "61") (name "Net-(L28-+)") (class "Default")
      (node (ref "K_28") (pin "2") (pinfunction "2_2") (pintype "passive"))
      (node (ref "L28") (pin "1") (pinfunction "+_1") (pintype "passive"))
    )
    (net (code "62") (name "Net-(L29-+)") (class "Default")
      (node (ref "K_29") (pin "2") (pinfunction "2_2") (pintype "passive"))
      (node (ref "L29") (pin "1") (pinfunction "+_1") (pintype "passive"))
    )
    (net (code "63") (name "Net-(L30-+)") (class "Default")
      (node (ref "K_30") (pin "2") (pinfunction "2_2") (pintype "passive"))
      (node (ref "L30") (pin "1") (pinfunction "+_1") (pintype "passive"))
    )
    (net (code "64") (name "Net-(L31-+)") (class "Default")
      (node (ref "K_31") (pin "2") (pinfunction "2_2") (pintype "passive"))
      (node (ref "L31") (pin "1") (pinfunction "+_1") (pintype "passive"))
    )
    (net (code "65") (name "Net-(L32-+)") (class "Default")
      (node (ref "K_32") (pin "2") (pinfunction "2_2") (pintype "passive"))
      (node (ref "L32") (pin "1") (pinfunction "+_1") (pintype "passive"))
    )
    (net (code "66") (name "Net-(L33-+)") (class "Default")
      (node (ref "K_33") (pin "2") (pinfunction "2_2") (pintype "passive"))
      (node (ref "L33") (pin "1") (pinfunction "+_1") (pintype "passive"))
    )
    (net (code "67") (name "Net-(L34-+)") (class "Default")
      (node (ref "K_34") (pin "2") (pinfunction "2_2") (pintype "passive"))
      (node (ref "L34") (pin "1") (pinfunction "+_1") (pintype "passive"))
    )
    (net (code "68") (name "Net-(L35-+)") (class "Default")
      (node (ref "K_35") (pin "2") (pinfunction "2_2") (pintype "passive"))
      (node (ref "L35") (pin "1") (pinfunction "+_1") (pintype "passive"))
    )
    (net (code "69") (name "Net-(L36-+)") (class "Default")
      (node (ref "K_36") (pin "2") (pinfunction "2_2") (pintype "passive"))
      (node (ref "L36") (pin "1") (pinfunction "+_1") (pintype "passive"))
    )
    (net (code "70") (name "Net-(L37-+)") (class "Default")
      (node (ref "K_37") (pin "2") (pinfunction "2_2") (pintype "passive"))
      (node (ref "L37") (pin "1") (pinfunction "+_1") (pintype "passive"))
    )
    (net (code "71") (name "Net-(L38-+)") (class "Default")
      (node (ref "K_38") (pin "2") (pinfunction "2_2") (pintype "passive"))
      (node (ref "L38") (pin "1") (pinfunction "+_1") (pintype "passive"))
    )
    (net (code "72") (name "Net-(L39-+)") (class "Default")
      (node (ref "K_39") (pin "2") (pinfunction "2_2") (pintype "passive"))
      (node (ref "L39") (pin "1") (pinfunction "+_1") (pintype "passive"))
    )
    (net (code "73") (name "Net-(L40-+)") (class "Default")
      (node (ref "K_40") (pin "2") (pinfunction "2_2") (pintype "passive"))
      (node (ref "L40") (pin "1") (pinfunction "+_1") (pintype "passive"))
    )
    (net (code "74") (name "Net-(L41-+)") (class "Default")
      (node (ref "K_41") (pin "2") (pinfunction "2_2") (pintype "passive"))
      (node (ref "L41") (pin "1") (pinfunction "+_1") (pintype "passive"))
    )
    (net (code "75") (name "Net-(L42-+)") (class "Default")
      (node (ref "K_42") (pin "2") (pinfunction "2_2") (pintype "passive"))
      (node (ref "L42") (pin "1") (pinfunction "+_1") (pintype "passive"))
    )
    (net (code "76") (name "Net-(L43-+)") (class "Default")
      (node (ref "K_43") (pin "2") (pinfunction "2_2") (pintype "passive"))
      (node (ref "L43") (pin "1") (pinfunction "+_1") (pintype "passive"))
    )
    (net (code "77") (name "Net-(L44-+)") (class "Default")
      (node (ref "K_44") (pin "2") (pinfunction "2_2") (pintype "passive"))
      (node (ref "L44") (pin "1") (pinfunction "+_1") (pintype "passive"))
    )
    (net (code "78") (name "Net-(L45-+)") (class "Default")
      (node (ref "K_45") (pin "2") (pinfunction "2_2") (pintype "passive"))
      (node (ref "L45") (pin "1") (pinfunction "+_1") (pintype "passive"))
    )
    (net (code "79") (name "Net-(L46-+)") (class "Default")
      (node (ref "K_46") (pin "2") (pinfunction "2_2") (pintype "passive"))
      (node (ref "L46") (pin "1") (pinfunction "+_1") (pintype "passive"))
    )
    (net (code "80") (name "Net-(L47-+)") (class "Default")
      (node (ref "K_47") (pin "2") (pinfunction "2_2") (pintype "passive"))
      (node (ref "L47") (pin "1") (pinfunction "+_1") (pintype "passive"))
    )
    (net (code "81") (name "Net-(L48-+)") (class "Default")
      (node (ref "K_48") (pin "2") (pinfunction "2_2") (pintype "passive"))
      (node (ref "L48") (pin "1") (pinfunction "+_1") (pintype "passive"))
    )
    (net (code "82") (name "Net-(L49-+)") (class "Default")
      (node (ref "K_49") (pin "2") (pinfunction "2_2") (pintype "passive"))
      (node (ref "L49") (pin "1") (pinfunction "+_1") (pintype "passive"))
    )
    (net (code "83") (name "Net-(L50-+)") (class "Default")
      (node (ref "K_50") (pin "2") (pinfunction "2_2") (pintype "passive"))
      (node (ref "L50") (pin "1") (pinfunction "+_1") (pintype "passive"))
    )
    (net (code "84") (name "Net-(L51-+)") (class "Default")
      (node (ref "K_51") (pin "2") (pinfunction "2_2") (pintype "passive"))
      (node (ref "L51") (pin "1") (pinfunction "+_1") (pintype "passive"))
    )
    (net (code "85") (name "Net-(L52-+)") (class "Default")
      (node (ref "K_52") (pin "2") (pinfunction "2_2") (pintype "passive"))
      (node (ref "L52") (pin "1") (pinfunction "+_1") (pintype "passive"))
    )
    (net (code "86") (name "Net-(L53-+)") (class "Default")
      (node (ref "K_53") (pin "2") (pinfunction "2_2") (pintype "passive"))
      (node (ref "L53") (pin "1") (pinfunction "+_1") (pintype "passive"))
    )
    (net (code "87") (name "Net-(L54-+)") (class "Default")
      (node (ref "K_54") (pin "2") (pinfunction "2_2") (pintype "passive"))
      (node (ref "L54") (pin "1") (pinfunction "+_1") (pintype "passive"))
    )
    (net (code "88") (name "Net-(L55-+)") (class "Default")
      (node (ref "K_55") (pin "2") (pinfunction "2_2") (pintype "passive"))
      (node (ref "L55") (pin "1") (pinfunction "+_1") (pintype "passive"))
    )
    (net (code "89") (name "Net-(L56-+)") (class "Default")
      (node (ref "K_56") (pin "2") (pinfunction "2_2") (pintype "passive"))
      (node (ref "L56") (pin "1") (pinfunction "+_1") (pintype "passive"))
    )
    (net (code "90") (name "Net-(L57-+)") (class "Default")
      (node (ref "K_57") (pin "2") (pinfunction "2_2") (pintype "passive"))
      (node (ref "L57") (pin "1") (pinfunction "+_1") (pintype "passive"))
    )
    (net (code "91") (name "Net-(L58-+)") (class "Default")
      (node (ref "K_58") (pin "2") (pinfunction "2_2") (pintype "passive"))
      (node (ref "L58") (pin "1") (pinfunction "+_1") (pintype "passive"))
    )
    (net (code "92") (name "Net-(L59-+)") (class "Default")
      (node (ref "K_59") (pin "2") (pinfunction "2_2") (pintype "passive"))
      (node (ref "L59") (pin "1") (pinfunction "+_1") (pintype "passive"))
    )
    (net (code "93") (name "Net-(L60-+)") (class "Default")
      (node (ref "K_60") (pin "2") (pinfunction "2_2") (pintype "passive"))
      (node (ref "L60") (pin "1") (pinfunction "+_1") (pintype "passive"))
    )
    (net (code "94") (name "Net-(L61-+)") (class "Default")
      (node (ref "K_61") (pin "2") (pinfunction "2_2") (pintype "passive"))
      (node (ref "L61") (pin "1") (pinfunction "+_1") (pintype "passive"))
    )
    (net (code "95") (name "Net-(L62-+)") (class "Default")
      (node (ref "K_62") (pin "2") (pinfunction "2_2") (pintype "passive"))
      (node (ref "L62") (pin "1") (pinfunction "+_1") (pintype "passive"))
    )
    (net (code "96") (name "Net-(L63-+)") (class "Default")
      (node (ref "K_63") (pin "2") (pinfunction "2_2") (pintype "passive"))
      (node (ref "L63") (pin "1") (pinfunction "+_1") (pintype "passive"))
    )
    (net (code "97") (name "Net-(L64-+)") (class "Default")
      (node (ref "K_64") (pin "2") (pinfunction "2_2") (pintype "passive"))
      (node (ref "L64") (pin "1") (pinfunction "+_1") (pintype "passive"))
    )
    (net (code "98") (name "Net-(L65-+)") (class "Default")
      (node (ref "K_65") (pin "2") (pinfunction "2_2") (pintype "passive"))
      (node (ref "L65") (pin "1") (pinfunction "+_1") (pintype "passive"))
    )
    (net (code "99") (name "Net-(L66-+)") (class "Default")
      (node (ref "K_66") (pin "2") (pinfunction "2_2") (pintype "passive"))
      (node (ref "L66") (pin "1") (pinfunction "+_1") (pintype "passive"))
    )
    (net (code "100") (name "Net-(L67-+)") (class "Default")
      (node (ref "K_67") (pin "2") (pinfunction "2_2") (pintype "passive"))
      (node (ref "L67") (pin "1") (pinfunction "+_1") (pintype "passive"))
    )
    (net (code "101") (name "Net-(L68-+)") (class "Default")
      (node (ref "K_68") (pin "2") (pinfunction "2_2") (pintype "passive"))
      (node (ref "L68") (pin "1") (pinfunction "+_1") (pintype "passive"))
    )
    (net (code "102") (name "Net-(M1-D+)") (class "Default")
      (node (ref "M1") (pin "3") (pinfunction "D+_3") (pintype "passive"))
      (node (ref "R4") (pin "1") (pintype "passive"))
    )
    (net (code "103") (name "Net-(M1-D-)") (class "Default")
      (node (ref "M1") (pin "4") (pinfunction "D-_4") (pintype "passive"))
      (node (ref "R3") (pin "1") (pintype "passive"))
    )
    (net (code "104") (name "Net-(U1-Ucap)") (class "Default")
      (node (ref "C1") (pin "2") (pintype "passive"))
      (node (ref "U1") (pin "6") (pinfunction "Ucap_6") (pintype "passive"))
    )
    (net (code "105") (name "Net-(U1-XTAL1)") (class "Default")
      (node (ref "U1") (pin "17") (pinfunction "XTAL1_17") (pintype "passive"))
      (node (ref "X1") (pin "3") (pinfunction "OUT_3") (pintype "passive"))
    )
    (net (code "106") (name "Net-(U1-XTAL2)") (class "Default")
      (node (ref "U1") (pin "16") (pinfunction "XTAL2_16") (pintype "passive"))
      (node (ref "X1") (pin "1") (pinfunction "IN_1") (pintype "passive"))
    )
    (net (code "107") (name "VCC") (class "Default")
      (node (ref "C2") (pin "2") (pintype "passive"))
      (node (ref "C3") (pin "2") (pintype "passive"))
      (node (ref "C4") (pin "2") (pintype "passive"))
      (node (ref "C5") (pin "2") (pintype "passive"))
      (node (ref "C6") (pin "2") (pintype "passive"))
      (node (ref "I") (pin "6") (pinfunction "VCC_6") (pintype "passive"))
      (node (ref "J2") (pin "1") (pinfunction "VCC_1") (pintype "passive"))
      (node (ref "M1") (pin "5") (pinfunction "VBUS_5") (pintype "passive"))
      (node (ref "R1") (pin "2") (pintype "passive"))
      (node (ref "U1") (pin "14") (pinfunction "VCC_14") (pintype "passive"))
      (node (ref "U1") (pin "2") (pinfunction "UVcc_2") (pintype "passive"))
      (node (ref "U1") (pin "24") (pinfunction "AVCC_24") (pintype "passive"))
      (node (ref "U1") (pin "34") (pinfunction "VCC_34") (pintype "passive"))
      (node (ref "U1") (pin "44") (pinfunction "AVCC_44") (pintype "passive"))
      (node (ref "U1") (pin "7") (pinfunction "VBus_7") (pintype "passive"))
    )
    (net (code "108") (name "unconnected-(K_1-Pad3)") (class "Default")
      (node (ref "K_1") (pin "3") (pinfunction "3_3") (pintype "passive+no_connect"))
    )
    (net (code "109") (name "unconnected-(K_1-Pad4)") (class "Default")
      (node (ref "K_1") (pin "4") (pinfunction "4_4") (pintype "passive+no_connect"))
    )
    (net (code "110") (name "unconnected-(K_2-Pad3)") (class "Default")
      (node (ref "K_2") (pin "3") (pinfunction "3_3") (pintype "passive+no_connect"))
    )
    (net (code "111") (name "unconnected-(K_2-Pad4)") (class "Default")
      (node (ref "K_2") (pin "4") (pinfunction "4_4") (pintype "passive+no_connect"))
    )
    (net (code "112") (name "unconnected-(K_3-Pad3)") (class "Default")
      (node (ref "K_3") (pin "3") (pinfunction "3_3") (pintype "passive+no_connect"))
    )
    (net (code "113") (name "unconnected-(K_3-Pad4)") (class "Default")
      (node (ref "K_3") (pin "4") (pinfunction "4_4") (pintype "passive+no_connect"))
    )
    (net (code "114") (name "unconnected-(K_4-Pad3)") (class "Default")
      (node (ref "K_4") (pin "3") (pinfunction "3_3") (pintype "passive+no_connect"))
    )
    (net (code "115") (name "unconnected-(K_4-Pad4)") (class "Default")
      (node (ref "K_4") (pin "4") (pinfunction "4_4") (pintype "passive+no_connect"))
    )
    (net (code "116") (name "unconnected-(K_5-Pad3)") (class "Default")
      (node (ref "K_5") (pin "3") (pinfunction "3_3") (pintype "passive+no_connect"))
    )
    (net (code "117") (name "unconnected-(K_5-Pad4)") (class "Default")
      (node (ref "K_5") (pin "4") (pinfunction "4_4") (pintype "passive+no_connect"))
    )
    (net (code "118") (name "unconnected-(K_6-Pad3)") (class "Default")
      (node (ref "K_6") (pin "3") (pinfunction "3_3") (pintype "passive+no_connect"))
    )
    (net (code "119") (name "unconnected-(K_6-Pad4)") (class "Default")
      (node (ref "K_6") (pin "4") (pinfunction "4_4") (pintype "passive+no_connect"))
    )
    (net (code "120") (name "unconnected-(K_7-Pad3)") (class "Default")
      (node (ref "K_7") (pin "3") (pinfunction "3_3") (pintype "passive+no_connect"))
    )
    (net (code "121") (name "unconnected-(K_7-Pad4)") (class "Default")
      (node (ref "K_7") (pin "4") (pinfunction "4_4") (pintype "passive+no_connect"))
    )
    (net (code "122") (name "unconnected-(K_8-Pad3)") (class "Default")
      (node (ref "K_8") (pin "3") (pinfunction "3_3") (pintype "passive+no_connect"))
    )
    (net (code "123") (name "unconnected-(K_8-Pad4)") (class "Default")
      (node (ref "K_8") (pin "4") (pinfunction "4_4") (pintype "passive+no_connect"))
    )
    (net (code "124") (name "unconnected-(K_9-Pad3)") (class "Default")
      (node (ref "K_9") (pin "3") (pinfunction "3_3") (pintype "passive+no_connect"))
    )
    (net (code "125") (name "unconnected-(K_9-Pad4)") (class "Default")
      (node (ref "K_9") (pin "4") (pinfunction "4_4") (pintype "passive+no_connect"))
    )
    (net (code "126") (name "unconnected-(K_10-Pad3)") (class "Default")
      (node (ref "K_10") (pin "3") (pinfunction "3_3") (pintype "passive+no_connect"))
    )
    (net (code "127") (name "unconnected-(K_10-Pad4)") (class "Default")
      (node (ref "K_10") (pin "4") (pinfunction "4_4") (pintype "passive+no_connect"))
    )
    (net (code "128") (name "unconnected-(K_11-Pad3)") (class "Default")
      (node (ref "K_11") (pin "3") (pinfunction "3_3") (pintype "passive+no_connect"))
    )
    (net (code "129") (name "unconnected-(K_11-Pad4)") (class "Default")
      (node (ref "K_11") (pin "4") (pinfunction "4_4") (pintype "passive+no_connect"))
    )
    (net (code "130") (name "unconnected-(K_12-Pad3)") (class "Default")
      (node (ref "K_12") (pin "3") (pinfunction "3_3") (pintype "passive+no_connect"))
    )
    (net (code "131") (name "unconnected-(K_12-Pad4)") (class "Default")
      (node (ref "K_12") (pin "4") (pinfunction "4_4") (pintype "passive+no_connect"))
    )
    (net (code "132") (name "unconnected-(K_13-Pad3)") (class "Default")
      (node (ref "K_13") (pin "3") (pinfunction "3_3") (pintype "passive+no_connect"))
    )
    (net (code "133") (name "unconnected-(K_13-Pad4)") (class "Default")
      (node (ref "K_13") (pin "4") (pinfunction "4_4") (pintype "passive+no_connect"))
    )
    (net (code "134") (name "unconnected-(K_14-Pad3)") (class "Default")
      (node (ref "K_14") (pin "3") (pinfunction "3_3") (pintype "passive+no_connect"))
    )
    (net (code "135") (name "unconnected-(K_14-Pad4)") (class "Default")
      (node (ref "K_14") (pin "4") (pinfunction "4_4") (pintype "passive+no_connect"))
    )
    (net (code "136") (name "unconnected-(K_15-Pad3)") (class "Default")
      (node (ref "K_15") (pin "3") (pinfunction "3_3") (pintype "passive+no_connect"))
    )
    (net (code "137") (name "unconnected-(K_15-Pad4)") (class "Default")
      (node (ref "K_15") (pin "4") (pinfunction "4_4") (pintype "passive+no_connect"))
    )
    (net (code "138") (name "unconnected-(K_16-Pad3)") (class "Default")
      (node (ref "K_16") (pin "3") (pinfunction "3_3") (pintype "passive+no_connect"))
    )
    (net (code "139") (name "unconnected-(K_16-Pad4)") (class "Default")
      (node (ref "K_16") (pin "4") (pinfunction "4_4") (pintype "passive+no_connect"))
    )
    (net (code "140") (name "unconnected-(K_17-Pad3)") (class "Default")
      (node (ref "K_17") (pin "3") (pinfunction "3_3") (pintype "passive+no_connect"))
    )
    (net (code "141") (name "unconnected-(K_17-Pad4)") (class "Default")
      (node (ref "K_17") (pin "4") (pinfunction "4_4") (pintype "passive+no_connect"))
    )
    (net (code "142") (name "unconnected-(K_18-Pad3)") (class "Default")
      (node (ref "K_18") (pin "3") (pinfunction "3_3") (pintype "passive+no_connect"))
    )
    (net (code "143") (name "unconnected-(K_18-Pad4)") (class "Default")
      (node (ref "K_18") (pin "4") (pinfunction "4_4") (pintype "passive+no_connect"))
    )
    (net (code "144") (name "unconnected-(K_19-Pad3)") (class "Default")
      (node (ref "K_19") (pin "3") (pinfunction "3_3") (pintype "passive+no_connect"))
    )
    (net (code "145") (name "unconnected-(K_19-Pad4)") (class "Default")
      (node (ref "K_19") (pin "4") (pinfunction "4_4") (pintype "passive+no_connect"))
    )
    (net (code "146") (name "unconnected-(K_20-Pad3)") (class "Default")
      (node (ref "K_20") (pin "3") (pinfunction "3_3") (pintype "passive+no_connect"))
    )
    (net (code "147") (name "unconnected-(K_20-Pad4)") (class "Default")
      (node (ref "K_20") (pin "4") (pinfunction "4_4") (pintype "passive+no_connect"))
    )
    (net (code "148") (name "unconnected-(K_21-Pad3)") (class "Default")
      (node (ref "K_21") (pin "3") (pinfunction "3_3") (pintype "passive+no_connect"))
    )
    (net (code "149") (name "unconnected-(K_21-Pad4)") (class "Default")
      (node (ref "K_21") (pin "4") (pinfunction "4_4") (pintype "passive+no_connect"))
    )
    (net (code "150") (name "unconnected-(K_22-Pad3)") (class "Default")
      (node (ref "K_22") (pin "3") (pinfunction "3_3") (pintype "passive+no_connect"))
    )
    (net (code "151") (name "unconnected-(K_22-Pad4)") (class "Default")
      (node (ref "K_22") (pin "4") (pinfunction "4_4") (pintype "passive+no_connect"))
    )
    (net (code "152") (name "unconnected-(K_23-Pad3)") (class "Default")
      (node (ref "K_23") (pin "3") (pinfunction "3_3") (pintype "passive+no_connect"))
    )
    (net (code "153") (name "unconnected-(K_23-Pad4)") (class "Default")
      (node (ref "K_23") (pin "4") (pinfunction "4_4") (pintype "passive+no_connect"))
    )
    (net (code "154") (name "unconnected-(K_24-Pad3)") (class "Default")
      (node (ref "K_24") (pin "3") (pinfunction "3_3") (pintype "passive+no_connect"))
    )
    (net (code "155") (name "unconnected-(K_24-Pad4)") (class "Default")
      (node (ref "K_24") (pin "4") (pinfunction "4_4") (pintype "passive+no_connect"))
    )
    (net (code "156") (name "unconnected-(K_25-Pad3)") (class "Default")
      (node (ref "K_25") (pin "3") (pinfunction "3_3") (pintype "passive+no_connect"))
    )
    (net (code "157") (name "unconnected-(K_25-Pad4)") (class "Default")
      (node (ref "K_25") (pin "4") (pinfunction "4_4") (pintype "passive+no_connect"))
    )
    (net (code "158") (name "unconnected-(K_26-Pad3)") (class "Default")
      (node (ref "K_26") (pin "3") (pinfunction "3_3") (pintype "passive+no_connect"))
    )
    (net (code "159") (name "unconnected-(K_26-Pad4)") (class "Default")
      (node (ref "K_26") (pin "4") (pinfunction "4_4") (pintype "passive+no_connect"))
    )
    (net (code "160") (name "unconnected-(K_27-Pad3)") (class "Default")
      (node (ref "K_27") (pin "3") (pinfunction "3_3") (pintype "passive+no_connect"))
    )
    (net (code "161") (name "unconnected-(K_27-Pad4)") (class "Default")
      (node (ref "K_27") (pin "4") (pinfunction "4_4") (pintype "passive+no_connect"))
    )
    (net (code "162") (name "unconnected-(K_28-Pad3)") (class "Default")
      (node (ref "K_28") (pin "3") (pinfunction "3_3") (pintype "passive+no_connect"))
    )
    (net (code "163") (name "unconnected-(K_28-Pad4)") (class "Default")
      (node (ref "K_28") (pin "4") (pinfunction "4_4") (pintype "passive+no_connect"))
    )
    (net (code "164") (name "unconnected-(K_30-Pad3)") (class "Default")
      (node (ref "K_30") (pin "3") (pinfunction "3_3") (pintype "passive+no_connect"))
    )
    (net (code "165") (name "unconnected-(K_30-Pad4)") (class "Default")
      (node (ref "K_30") (pin "4") (pinfunction "4_4") (pintype "passive+no_connect"))
    )
    (net (code "166") (name "unconnected-(K_31-Pad3)") (class "Default")
      (node (ref "K_31") (pin "3") (pinfunction "3_3") (pintype "passive+no_connect"))
    )
    (net (code "167") (name "unconnected-(K_31-Pad4)") (class "Default")
      (node (ref "K_31") (pin "4") (pinfunction "4_4") (pintype "passive+no_connect"))
    )
    (net (code "168") (name "unconnected-(K_32-Pad3)") (class "Default")
      (node (ref "K_32") (pin "3") (pinfunction "3_3") (pintype "passive+no_connect"))
    )
    (net (code "169") (name "unconnected-(K_32-Pad4)") (class "Default")
      (node (ref "K_32") (pin "4") (pinfunction "4_4") (pintype "passive+no_connect"))
    )
    (net (code "170") (name "unconnected-(K_33-Pad3)") (class "Default")
      (node (ref "K_33") (pin "3") (pinfunction "3_3") (pintype "passive+no_connect"))
    )
    (net (code "171") (name "unconnected-(K_33-Pad4)") (class "Default")
      (node (ref "K_33") (pin "4") (pinfunction "4_4") (pintype "passive+no_connect"))
    )
    (net (code "172") (name "unconnected-(K_34-Pad3)") (class "Default")
      (node (ref "K_34") (pin "3") (pinfunction "3_3") (pintype "passive+no_connect"))
    )
    (net (code "173") (name "unconnected-(K_34-Pad4)") (class "Default")
      (node (ref "K_34") (pin "4") (pinfunction "4_4") (pintype "passive+no_connect"))
    )
    (net (code "174") (name "unconnected-(K_35-Pad3)") (class "Default")
      (node (ref "K_35") (pin "3") (pinfunction "3_3") (pintype "passive+no_connect"))
    )
    (net (code "175") (name "unconnected-(K_35-Pad4)") (class "Default")
      (node (ref "K_35") (pin "4") (pinfunction "4_4") (pintype "passive+no_connect"))
    )
    (net (code "176") (name "unconnected-(K_36-Pad3)") (class "Default")
      (node (ref "K_36") (pin "3") (pinfunction "3_3") (pintype "passive+no_connect"))
    )
    (net (code "177") (name "unconnected-(K_36-Pad4)") (class "Default")
      (node (ref "K_36") (pin "4") (pinfunction "4_4") (pintype "passive+no_connect"))
    )
    (net (code "178") (name "unconnected-(K_37-Pad3)") (class "Default")
      (node (ref "K_37") (pin "3") (pinfunction "3_3") (pintype "passive+no_connect"))
    )
    (net (code "179") (name "unconnected-(K_37-Pad4)") (class "Default")
      (node (ref "K_37") (pin "4") (pinfunction "4_4") (pintype "passive+no_connect"))
    )
    (net (code "180") (name "unconnected-(K_38-Pad3)") (class "Default")
      (node (ref "K_38") (pin "3") (pinfunction "3_3") (pintype "passive+no_connect"))
    )
    (net (code "181") (name "unconnected-(K_38-Pad4)") (class "Default")
      (node (ref "K_38") (pin "4") (pinfunction "4_4") (pintype "passive+no_connect"))
    )
    (net (code "182") (name "unconnected-(K_39-Pad3)") (class "Default")
      (node (ref "K_39") (pin "3") (pinfunction "3_3") (pintype "passive+no_connect"))
    )
    (net (code "183") (name "unconnected-(K_39-Pad4)") (class "Default")
      (node (ref "K_39") (pin "4") (pinfunction "4_4") (pintype "passive+no_connect"))
    )
    (net (code "184") (name "unconnected-(K_40-Pad3)") (class "Default")
      (node (ref "K_40") (pin "3") (pinfunction "3_3") (pintype "passive+no_connect"))
    )
    (net (code "185") (name "unconnected-(K_40-Pad4)") (class "Default")
      (node (ref "K_40") (pin "4") (pinfunction "4_4") (pintype "passive+no_connect"))
    )
    (net (code "186") (name "unconnected-(K_41-Pad3)") (class "Default")
      (node (ref "K_41") (pin "3") (pinfunction "3_3") (pintype "passive+no_connect"))
    )
    (net (code "187") (name "unconnected-(K_41-Pad4)") (class "Default")
      (node (ref "K_41") (pin "4") (pinfunction "4_4") (pintype "passive+no_connect"))
    )
    (net (code "188") (name "unconnected-(K_42-Pad3)") (class "Default")
      (node (ref "K_42") (pin "3") (pinfunction "3_3") (pintype "passive+no_connect"))
    )
    (net (code "189") (name "unconnected-(K_42-Pad4)") (class "Default")
      (node (ref "K_42") (pin "4") (pinfunction "4_4") (pintype "passive+no_connect"))
    )
    (net (code "190") (name "unconnected-(K_43-Pad3)") (class "Default")
      (node (ref "K_43") (pin "3") (pinfunction "3_3") (pintype "passive+no_connect"))
    )
    (net (code "191") (name "unconnected-(K_43-Pad4)") (class "Default")
      (node (ref "K_43") (pin "4") (pinfunction "4_4") (pintype "passive+no_connect"))
    )
    (net (code "192") (name "unconnected-(K_44-Pad3)") (class "Default")
      (node (ref "K_44") (pin "3") (pinfunction "3_3") (pintype "passive+no_connect"))
    )
    (net (code "193") (name "unconnected-(K_44-Pad4)") (class "Default")
      (node (ref "K_44") (pin "4") (pinfunction "4_4") (pintype "passive+no_connect"))
    )
    (net (code "194") (name "unconnected-(K_45-Pad3)") (class "Default")
      (node (ref "K_45") (pin "3") (pinfunction "3_3") (pintype "passive+no_connect"))
    )
    (net (code "195") (name "unconnected-(K_45-Pad4)") (class "Default")
      (node (ref "K_45") (pin "4") (pinfunction "4_4") (pintype "passive+no_connect"))
    )
    (net (code "196") (name "unconnected-(K_46-Pad3)") (class "Default")
      (node (ref "K_46") (pin "3") (pinfunction "3_3") (pintype "passive+no_connect"))
    )
    (net (code "197") (name "unconnected-(K_46-Pad4)") (class "Default")
      (node (ref "K_46") (pin "4") (pinfunction "4_4") (pintype "passive+no_connect"))
    )
    (net (code "198") (name "unconnected-(K_47-Pad3)") (class "Default")
      (node (ref "K_47") (pin "3") (pinfunction "3_3") (pintype "passive+no_connect"))
    )
    (net (code "199") (name "unconnected-(K_47-Pad4)") (class "Default")
      (node (ref "K_47") (pin "4") (pinfunction "4_4") (pintype "passive+no_connect"))
    )
    (net (code "200") (name "unconnected-(K_48-Pad3)") (class "Default")
      (node (ref "K_48") (pin "3") (pinfunction "3_3") (pintype "passive+no_connect"))
    )
    (net (code "201") (name "unconnected-(K_48-Pad4)") (class "Default")
      (node (ref "K_48") (pin "4") (pinfunction "4_4") (pintype "passive+no_connect"))
    )
    (net (code "202") (name "unconnected-(K_49-Pad3)") (class "Default")
      (node (ref "K_49") (pin "3") (pinfunction "3_3") (pintype "passive+no_connect"))
    )
    (net (code "203") (name "unconnected-(K_49-Pad4)") (class "Default")
      (node (ref "K_49") (pin "4") (pinfunction "4_4") (pintype "passive+no_connect"))
    )
    (net (code "204") (name "unconnected-(K_50-Pad3)") (class "Default")
      (node (ref "K_50") (pin "3") (pinfunction "3_3") (pintype "passive+no_connect"))
    )
    (net (code "205") (name "unconnected-(K_50-Pad4)") (class "Default")
      (node (ref "K_50") (pin "4") (pinfunction "4_4") (pintype "passive+no_connect"))
    )
    (net (code "206") (name "unconnected-(K_51-Pad3)") (class "Default")
      (node (ref "K_51") (pin "3") (pinfunction "3_3") (pintype "passive+no_connect"))
    )
    (net (code "207") (name "unconnected-(K_51-Pad4)") (class "Default")
      (node (ref "K_51") (pin "4") (pinfunction "4_4") (pintype "passive+no_connect"))
    )
    (net (code "208") (name "unconnected-(K_52-Pad3)") (class "Default")
      (node (ref "K_52") (pin "3") (pinfunction "3_3") (pintype "passive+no_connect"))
    )
    (net (code "209") (name "unconnected-(K_52-Pad4)") (class "Default")
      (node (ref "K_52") (pin "4") (pinfunction "4_4") (pintype "passive+no_connect"))
    )
    (net (code "210") (name "unconnected-(K_53-Pad3)") (class "Default")
      (node (ref "K_53") (pin "3") (pinfunction "3_3") (pintype "passive+no_connect"))
    )
    (net (code "211") (name "unconnected-(K_53-Pad4)") (class "Default")
      (node (ref "K_53") (pin "4") (pinfunction "4_4") (pintype "passive+no_connect"))
    )
    (net (code "212") (name "unconnected-(K_54-Pad3)") (class "Default")
      (node (ref "K_54") (pin "3") (pinfunction "3_3") (pintype "passive+no_connect"))
    )
    (net (code "213") (name "unconnected-(K_54-Pad4)") (class "Default")
      (node (ref "K_54") (pin "4") (pinfunction "4_4") (pintype "passive+no_connect"))
    )
    (net (code "214") (name "unconnected-(K_55-Pad3)") (class "Default")
      (node (ref "K_55") (pin "3") (pinfunction "3_3") (pintype "passive+no_connect"))
    )
    (net (code "215") (name "unconnected-(K_55-Pad4)") (class "Default")
      (node (ref "K_55") (pin "4") (pinfunction "4_4") (pintype "passive+no_connect"))
    )
    (net (code "216") (name "unconnected-(K_56-Pad3)") (class "Default")
      (node (ref "K_56") (pin "3") (pinfunction "3_3") (pintype "passive+no_connect"))
    )
    (net (code "217") (name "unconnected-(K_56-Pad4)") (class "Default")
      (node (ref "K_56") (pin "4") (pinfunction "4_4") (pintype "passive+no_connect"))
    )
    (net (code "218") (name "unconnected-(K_57-Pad3)") (class "Default")
      (node (ref "K_57") (pin "3") (pinfunction "3_3") (pintype "passive+no_connect"))
    )
    (net (code "219") (name "unconnected-(K_57-Pad4)") (class "Default")
      (node (ref "K_57") (pin "4") (pinfunction "4_4") (pintype "passive+no_connect"))
    )
    (net (code "220") (name "unconnected-(K_58-Pad3)") (class "Default")
      (node (ref "K_58") (pin "3") (pinfunction "3_3") (pintype "passive+no_connect"))
    )
    (net (code "221") (name "unconnected-(K_58-Pad4)") (class "Default")
      (node (ref "K_58") (pin "4") (pinfunction "4_4") (pintype "passive+no_connect"))
    )
    (net (code "222") (name "unconnected-(K_59-Pad3)") (class "Default")
      (node (ref "K_59") (pin "3") (pinfunction "3_3") (pintype "passive+no_connect"))
    )
    (net (code "223") (name "unconnected-(K_59-Pad4)") (class "Default")
      (node (ref "K_59") (pin "4") (pinfunction "4_4") (pintype "passive+no_connect"))
    )
    (net (code "224") (name "unconnected-(K_60-Pad3)") (class "Default")
      (node (ref "K_60") (pin "3") (pinfunction "3_3") (pintype "passive+no_connect"))
    )
    (net (code "225") (name "unconnected-(K_60-Pad4)") (class "Default")
      (node (ref "K_60") (pin "4") (pinfunction "4_4") (pintype "passive+no_connect"))
    )
    (net (code "226") (name "unconnected-(K_61-Pad3)") (class "Default")
      (node (ref "K_61") (pin "3") (pinfunction "3_3") (pintype "passive+no_connect"))
    )
    (net (code "227") (name "unconnected-(K_61-Pad4)") (class "Default")
      (node (ref "K_61") (pin "4") (pinfunction "4_4") (pintype "passive+no_connect"))
    )
    (net (code "228") (name "unconnected-(K_62-Pad3)") (class "Default")
      (node (ref "K_62") (pin "3") (pinfunction "3_3") (pintype "passive"))
    )
    (net (code "229") (name "unconnected-(K_62-Pad4)") (class "Default")
      (node (ref "K_62") (pin "4") (pinfunction "4_4") (pintype "passive"))
    )
    (net (code "230") (name "unconnected-(K_63-Pad3)") (class "Default")
      (node (ref "K_63") (pin "3") (pinfunction "3_3") (pintype "passive"))
    )
    (net (code "231") (name "unconnected-(K_63-Pad4)") (class "Default")
      (node (ref "K_63") (pin "4") (pinfunction "4_4") (pintype "passive"))
    )
    (net (code "232") (name "unconnected-(K_64-Pad3)") (class "Default")
      (node (ref "K_64") (pin "3") (pinfunction "3_3") (pintype "passive"))
    )
    (net (code "233") (name "unconnected-(K_64-Pad4)") (class "Default")
      (node (ref "K_64") (pin "4") (pinfunction "4_4") (pintype "passive"))
    )
    (net (code "234") (name "unconnected-(K_65-Pad3)") (class "Default")
      (node (ref "K_65") (pin "3") (pinfunction "3_3") (pintype "passive"))
    )
    (net (code "235") (name "unconnected-(K_65-Pad4)") (class "Default")
      (node (ref "K_65") (pin "4") (pinfunction "4_4") (pintype "passive"))
    )
    (net (code "236") (name "unconnected-(K_66-Pad3)") (class "Default")
      (node (ref "K_66") (pin "3") (pinfunction "3_3") (pintype "passive"))
    )
    (net (code "237") (name "unconnected-(K_66-Pad4)") (class "Default")
      (node (ref "K_66") (pin "4") (pinfunction "4_4") (pintype "passive"))
    )
    (net (code "238") (name "unconnected-(K_67-Pad3)") (class "Default")
      (node (ref "K_67") (pin "3") (pinfunction "3_3") (pintype "passive"))
    )
    (net (code "239") (name "unconnected-(K_67-Pad4)") (class "Default")
      (node (ref "K_67") (pin "4") (pinfunction "4_4") (pintype "passive"))
    )
    (net (code "240") (name "unconnected-(K_68-Pad3)") (class "Default")
      (node (ref "K_68") (pin "3") (pinfunction "3_3") (pintype "passive"))
    )
    (net (code "241") (name "unconnected-(K_68-Pad4)") (class "Default")
      (node (ref "K_68") (pin "4") (pinfunction "4_4") (pintype "passive"))
    )
    (net (code "242") (name "unconnected-(M1-ID-Pad2)") (class "Default")
      (node (ref "M1") (pin "2") (pinfunction "ID_2") (pintype "passive"))
    )
    (net (code "243") (name "unconnected-(U1-AREF-Pad42)") (class "Default")
      (node (ref "U1") (pin "42") (pinfunction "AREF_42") (pintype "passive+no_connect"))
    )
  )
)
